# schematic3.net
KiCad netlist of a schematic drawn in EAGLE
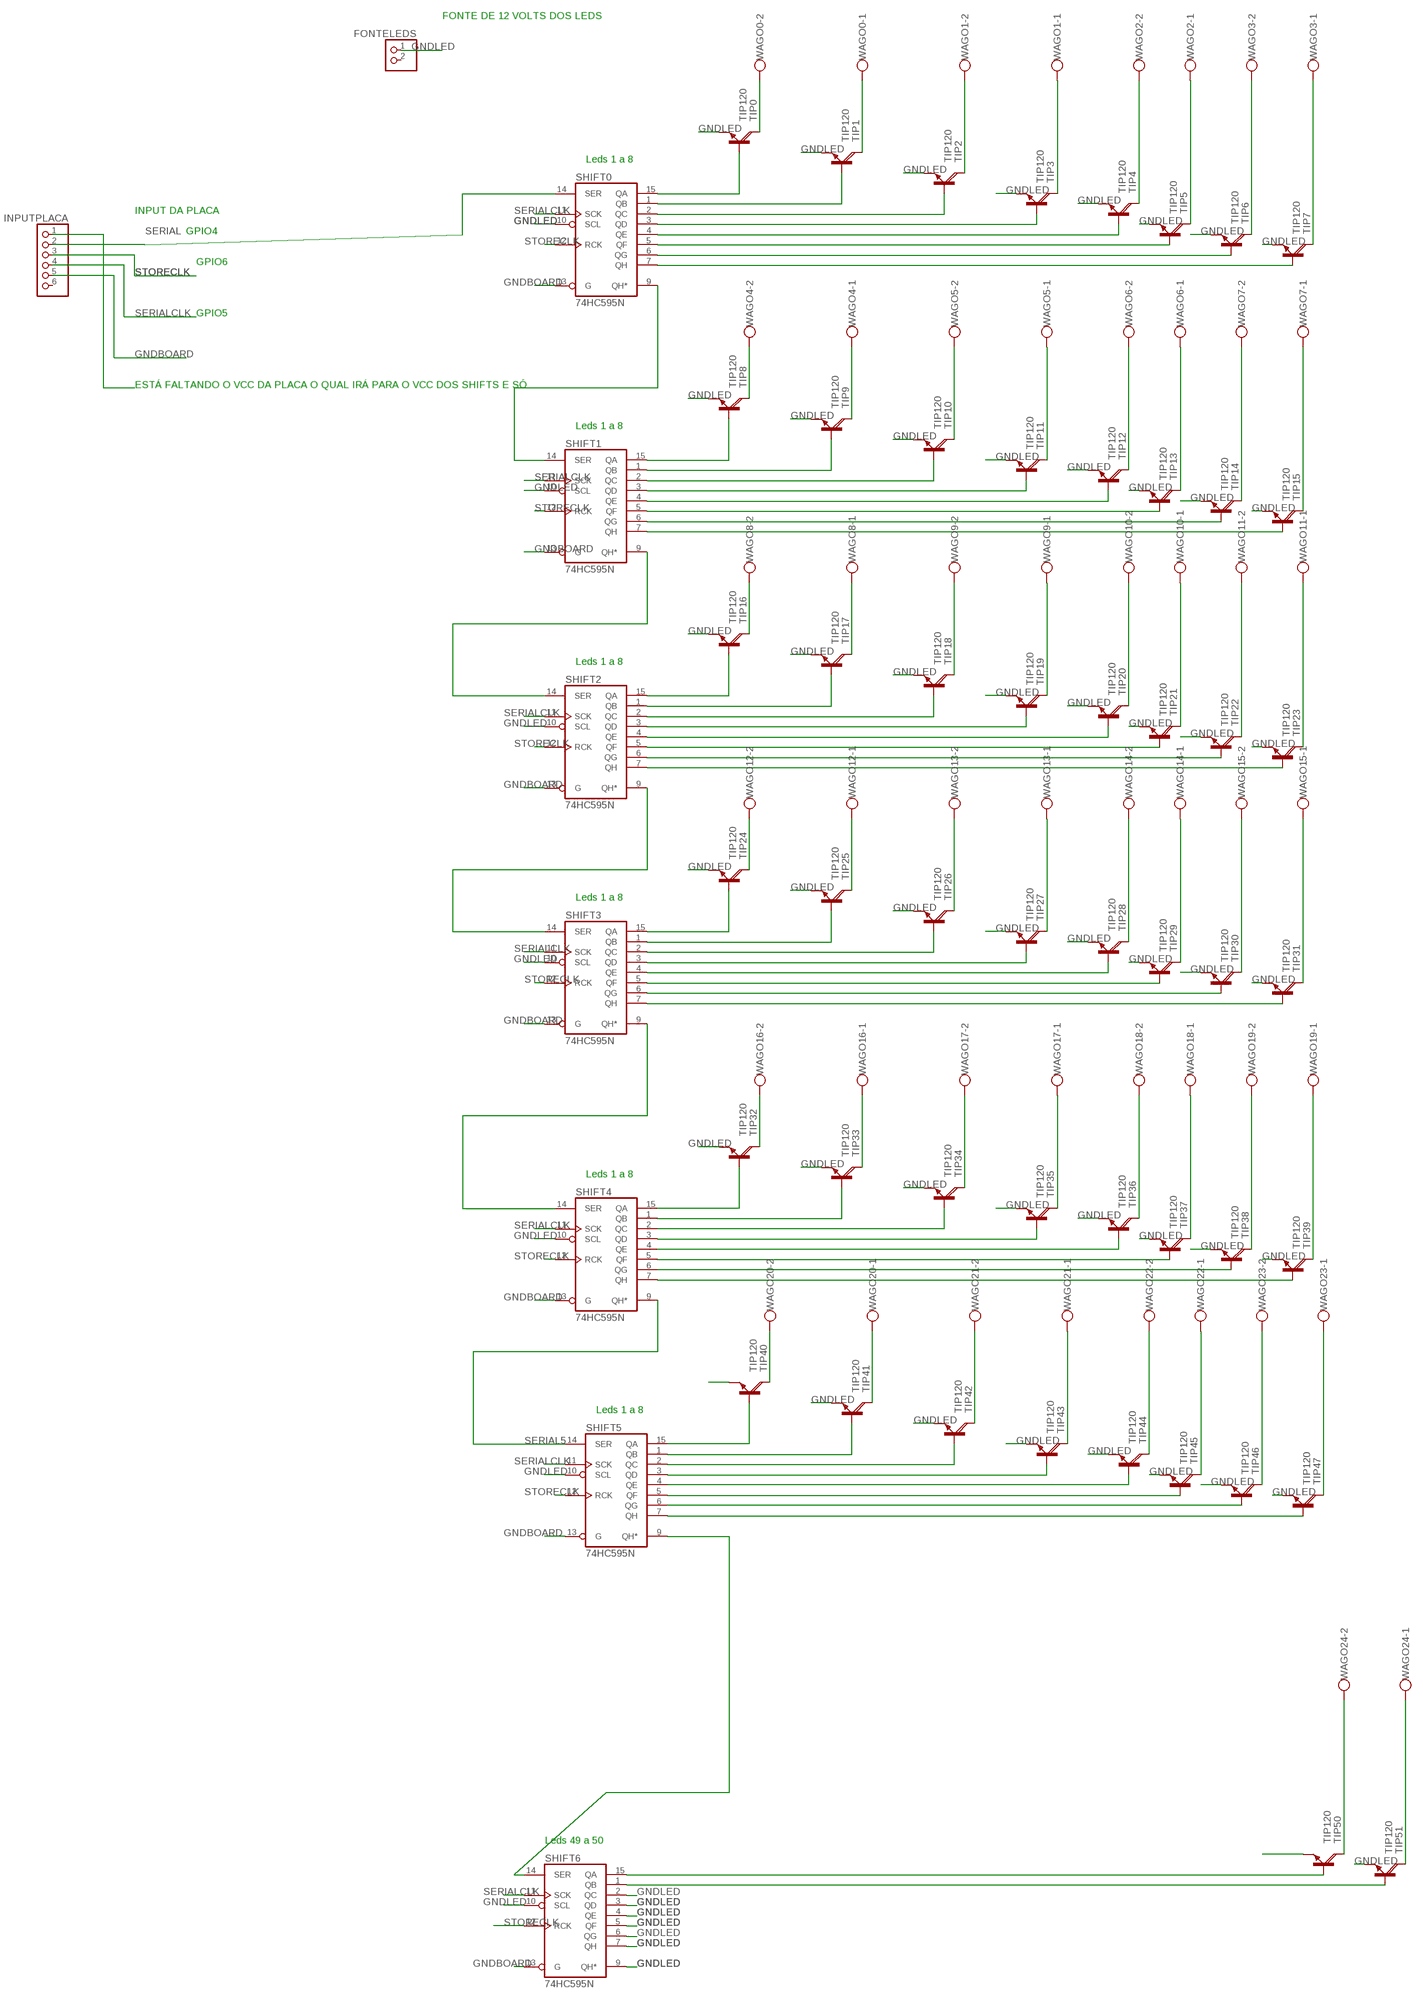
[diagram p0: schematic, sheet 1]

(export (version "E")
  (design (tool "Eeschema 10.0.6"))
  (components
    (comp (ref "FONTELEDS")
      (value "PINHD-1X2")
      (footprint "eagle-import:1X02")
      (libsource (lib "eagle-import") (part "PINHD-1X2"))
    )
    (comp (ref "INPUTPLACA")
      (value "PINHD-1X6")
      (footprint "eagle-import:1X06")
      (libsource (lib "eagle-import") (part "PINHD-1X6"))
    )
    (comp (ref "SHIFT0")
      (value "74HC595N")
      (footprint "eagle-import:DIL16")
      (libsource (lib "eagle-import") (part "74595NHC"))
    )
    (comp (ref "SHIFT1")
      (value "74HC595N")
      (footprint "eagle-import:DIL16")
      (libsource (lib "eagle-import") (part "74595NHC"))
    )
    (comp (ref "SHIFT2")
      (value "74HC595N")
      (footprint "eagle-import:DIL16")
      (libsource (lib "eagle-import") (part "74595NHC"))
    )
    (comp (ref "SHIFT3")
      (value "74HC595N")
      (footprint "eagle-import:DIL16")
      (libsource (lib "eagle-import") (part "74595NHC"))
    )
    (comp (ref "SHIFT4")
      (value "74HC595N")
      (footprint "eagle-import:DIL16")
      (libsource (lib "eagle-import") (part "74595NHC"))
    )
    (comp (ref "SHIFT5")
      (value "74HC595N")
      (footprint "eagle-import:DIL16")
      (libsource (lib "eagle-import") (part "74595NHC"))
    )
    (comp (ref "SHIFT6")
      (value "74HC595N")
      (footprint "eagle-import:DIL16")
      (libsource (lib "eagle-import") (part "74595NHC"))
    )
    (comp (ref "TIP0")
      (value "TIP120")
      (footprint "eagle-import:TO220AH")
      (libsource (lib "eagle-import") (part "TIP120"))
    )
    (comp (ref "TIP1")
      (value "TIP120")
      (footprint "eagle-import:TO220AH")
      (libsource (lib "eagle-import") (part "TIP120"))
    )
    (comp (ref "TIP2")
      (value "TIP120")
      (footprint "eagle-import:TO220AH")
      (libsource (lib "eagle-import") (part "TIP120"))
    )
    (comp (ref "TIP3")
      (value "TIP120")
      (footprint "eagle-import:TO220AH")
      (libsource (lib "eagle-import") (part "TIP120"))
    )
    (comp (ref "TIP4")
      (value "TIP120")
      (footprint "eagle-import:TO220AH")
      (libsource (lib "eagle-import") (part "TIP120"))
    )
    (comp (ref "TIP5")
      (value "TIP120")
      (footprint "eagle-import:TO220AH")
      (libsource (lib "eagle-import") (part "TIP120"))
    )
    (comp (ref "TIP6")
      (value "TIP120")
      (footprint "eagle-import:TO220AH")
      (libsource (lib "eagle-import") (part "TIP120"))
    )
    (comp (ref "TIP7")
      (value "TIP120")
      (footprint "eagle-import:TO220AH")
      (libsource (lib "eagle-import") (part "TIP120"))
    )
    (comp (ref "TIP8")
      (value "TIP120")
      (footprint "eagle-import:TO220AH")
      (libsource (lib "eagle-import") (part "TIP120"))
    )
    (comp (ref "TIP9")
      (value "TIP120")
      (footprint "eagle-import:TO220AH")
      (libsource (lib "eagle-import") (part "TIP120"))
    )
    (comp (ref "TIP10")
      (value "TIP120")
      (footprint "eagle-import:TO220AH")
      (libsource (lib "eagle-import") (part "TIP120"))
    )
    (comp (ref "TIP11")
      (value "TIP120")
      (footprint "eagle-import:TO220AH")
      (libsource (lib "eagle-import") (part "TIP120"))
    )
    (comp (ref "TIP12")
      (value "TIP120")
      (footprint "eagle-import:TO220AH")
      (libsource (lib "eagle-import") (part "TIP120"))
    )
    (comp (ref "TIP13")
      (value "TIP120")
      (footprint "eagle-import:TO220AH")
      (libsource (lib "eagle-import") (part "TIP120"))
    )
    (comp (ref "TIP14")
      (value "TIP120")
      (footprint "eagle-import:TO220AH")
      (libsource (lib "eagle-import") (part "TIP120"))
    )
    (comp (ref "TIP15")
      (value "TIP120")
      (footprint "eagle-import:TO220AH")
      (libsource (lib "eagle-import") (part "TIP120"))
    )
    (comp (ref "TIP16")
      (value "TIP120")
      (footprint "eagle-import:TO220AH")
      (libsource (lib "eagle-import") (part "TIP120"))
    )
    (comp (ref "TIP17")
      (value "TIP120")
      (footprint "eagle-import:TO220AH")
      (libsource (lib "eagle-import") (part "TIP120"))
    )
    (comp (ref "TIP18")
      (value "TIP120")
      (footprint "eagle-import:TO220AH")
      (libsource (lib "eagle-import") (part "TIP120"))
    )
    (comp (ref "TIP19")
      (value "TIP120")
      (footprint "eagle-import:TO220AH")
      (libsource (lib "eagle-import") (part "TIP120"))
    )
    (comp (ref "TIP20")
      (value "TIP120")
      (footprint "eagle-import:TO220AH")
      (libsource (lib "eagle-import") (part "TIP120"))
    )
    (comp (ref "TIP21")
      (value "TIP120")
      (footprint "eagle-import:TO220AH")
      (libsource (lib "eagle-import") (part "TIP120"))
    )
    (comp (ref "TIP22")
      (value "TIP120")
      (footprint "eagle-import:TO220AH")
      (libsource (lib "eagle-import") (part "TIP120"))
    )
    (comp (ref "TIP23")
      (value "TIP120")
      (footprint "eagle-import:TO220AH")
      (libsource (lib "eagle-import") (part "TIP120"))
    )
    (comp (ref "TIP24")
      (value "TIP120")
      (footprint "eagle-import:TO220AH")
      (libsource (lib "eagle-import") (part "TIP120"))
    )
    (comp (ref "TIP25")
      (value "TIP120")
      (footprint "eagle-import:TO220AH")
      (libsource (lib "eagle-import") (part "TIP120"))
    )
    (comp (ref "TIP26")
      (value "TIP120")
      (footprint "eagle-import:TO220AH")
      (libsource (lib "eagle-import") (part "TIP120"))
    )
    (comp (ref "TIP27")
      (value "TIP120")
      (footprint "eagle-import:TO220AH")
      (libsource (lib "eagle-import") (part "TIP120"))
    )
    (comp (ref "TIP28")
      (value "TIP120")
      (footprint "eagle-import:TO220AH")
      (libsource (lib "eagle-import") (part "TIP120"))
    )
    (comp (ref "TIP29")
      (value "TIP120")
      (footprint "eagle-import:TO220AH")
      (libsource (lib "eagle-import") (part "TIP120"))
    )
    (comp (ref "TIP30")
      (value "TIP120")
      (footprint "eagle-import:TO220AH")
      (libsource (lib "eagle-import") (part "TIP120"))
    )
    (comp (ref "TIP31")
      (value "TIP120")
      (footprint "eagle-import:TO220AH")
      (libsource (lib "eagle-import") (part "TIP120"))
    )
    (comp (ref "TIP32")
      (value "TIP120")
      (footprint "eagle-import:TO220AH")
      (libsource (lib "eagle-import") (part "TIP120"))
    )
    (comp (ref "TIP33")
      (value "TIP120")
      (footprint "eagle-import:TO220AH")
      (libsource (lib "eagle-import") (part "TIP120"))
    )
    (comp (ref "TIP34")
      (value "TIP120")
      (footprint "eagle-import:TO220AH")
      (libsource (lib "eagle-import") (part "TIP120"))
    )
    (comp (ref "TIP35")
      (value "TIP120")
      (footprint "eagle-import:TO220AH")
      (libsource (lib "eagle-import") (part "TIP120"))
    )
    (comp (ref "TIP36")
      (value "TIP120")
      (footprint "eagle-import:TO220AH")
      (libsource (lib "eagle-import") (part "TIP120"))
    )
    (comp (ref "TIP37")
      (value "TIP120")
      (footprint "eagle-import:TO220AH")
      (libsource (lib "eagle-import") (part "TIP120"))
    )
    (comp (ref "TIP38")
      (value "TIP120")
      (footprint "eagle-import:TO220AH")
      (libsource (lib "eagle-import") (part "TIP120"))
    )
    (comp (ref "TIP39")
      (value "TIP120")
      (footprint "eagle-import:TO220AH")
      (libsource (lib "eagle-import") (part "TIP120"))
    )
    (comp (ref "TIP40")
      (value "TIP120")
      (footprint "eagle-import:TO220AH")
      (libsource (lib "eagle-import") (part "TIP120"))
    )
    (comp (ref "TIP41")
      (value "TIP120")
      (footprint "eagle-import:TO220AH")
      (libsource (lib "eagle-import") (part "TIP120"))
    )
    (comp (ref "TIP42")
      (value "TIP120")
      (footprint "eagle-import:TO220AH")
      (libsource (lib "eagle-import") (part "TIP120"))
    )
    (comp (ref "TIP43")
      (value "TIP120")
      (footprint "eagle-import:TO220AH")
      (libsource (lib "eagle-import") (part "TIP120"))
    )
    (comp (ref "TIP44")
      (value "TIP120")
      (footprint "eagle-import:TO220AH")
      (libsource (lib "eagle-import") (part "TIP120"))
    )
    (comp (ref "TIP45")
      (value "TIP120")
      (footprint "eagle-import:TO220AH")
      (libsource (lib "eagle-import") (part "TIP120"))
    )
    (comp (ref "TIP46")
      (value "TIP120")
      (footprint "eagle-import:TO220AH")
      (libsource (lib "eagle-import") (part "TIP120"))
    )
    (comp (ref "TIP47")
      (value "TIP120")
      (footprint "eagle-import:TO220AH")
      (libsource (lib "eagle-import") (part "TIP120"))
    )
    (comp (ref "TIP50")
      (value "TIP120")
      (footprint "eagle-import:TO220AH")
      (libsource (lib "eagle-import") (part "TIP120"))
    )
    (comp (ref "TIP51")
      (value "TIP120")
      (footprint "eagle-import:TO220AH")
      (libsource (lib "eagle-import") (part "TIP120"))
    )
    (comp (ref "WAGO0")
      (value "W237-102")
      (footprint "eagle-import:W237-102")
      (fields (field (name "MPN") "237-102"))
      (libsource (lib "eagle-import") (part "W237-102"))
    )
    (comp (ref "WAGO1")
      (value "W237-102")
      (footprint "eagle-import:W237-102")
      (fields (field (name "MPN") "237-102"))
      (libsource (lib "eagle-import") (part "W237-102"))
    )
    (comp (ref "WAGO2")
      (value "W237-102")
      (footprint "eagle-import:W237-102")
      (fields (field (name "MPN") "237-102"))
      (libsource (lib "eagle-import") (part "W237-102"))
    )
    (comp (ref "WAGO3")
      (value "W237-102")
      (footprint "eagle-import:W237-102")
      (fields (field (name "MPN") "237-102"))
      (libsource (lib "eagle-import") (part "W237-102"))
    )
    (comp (ref "WAGO4")
      (value "W237-102")
      (footprint "eagle-import:W237-102")
      (fields (field (name "MPN") "237-102"))
      (libsource (lib "eagle-import") (part "W237-102"))
    )
    (comp (ref "WAGO5")
      (value "W237-102")
      (footprint "eagle-import:W237-102")
      (fields (field (name "MPN") "237-102"))
      (libsource (lib "eagle-import") (part "W237-102"))
    )
    (comp (ref "WAGO6")
      (value "W237-102")
      (footprint "eagle-import:W237-102")
      (fields (field (name "MPN") "237-102"))
      (libsource (lib "eagle-import") (part "W237-102"))
    )
    (comp (ref "WAGO7")
      (value "W237-102")
      (footprint "eagle-import:W237-102")
      (fields (field (name "MPN") "237-102"))
      (libsource (lib "eagle-import") (part "W237-102"))
    )
    (comp (ref "WAGO8")
      (value "W237-102")
      (footprint "eagle-import:W237-102")
      (fields (field (name "MPN") "237-102"))
      (libsource (lib "eagle-import") (part "W237-102"))
    )
    (comp (ref "WAGO9")
      (value "W237-102")
      (footprint "eagle-import:W237-102")
      (fields (field (name "MPN") "237-102"))
      (libsource (lib "eagle-import") (part "W237-102"))
    )
    (comp (ref "WAGO10")
      (value "W237-102")
      (footprint "eagle-import:W237-102")
      (fields (field (name "MPN") "237-102"))
      (libsource (lib "eagle-import") (part "W237-102"))
    )
    (comp (ref "WAGO11")
      (value "W237-102")
      (footprint "eagle-import:W237-102")
      (fields (field (name "MPN") "237-102"))
      (libsource (lib "eagle-import") (part "W237-102"))
    )
    (comp (ref "WAGO12")
      (value "W237-102")
      (footprint "eagle-import:W237-102")
      (fields (field (name "MPN") "237-102"))
      (libsource (lib "eagle-import") (part "W237-102"))
    )
    (comp (ref "WAGO13")
      (value "W237-102")
      (footprint "eagle-import:W237-102")
      (fields (field (name "MPN") "237-102"))
      (libsource (lib "eagle-import") (part "W237-102"))
    )
    (comp (ref "WAGO14")
      (value "W237-102")
      (footprint "eagle-import:W237-102")
      (fields (field (name "MPN") "237-102"))
      (libsource (lib "eagle-import") (part "W237-102"))
    )
    (comp (ref "WAGO15")
      (value "W237-102")
      (footprint "eagle-import:W237-102")
      (fields (field (name "MPN") "237-102"))
      (libsource (lib "eagle-import") (part "W237-102"))
    )
    (comp (ref "WAGO16")
      (value "W237-102")
      (footprint "eagle-import:W237-102")
      (fields (field (name "MPN") "237-102"))
      (libsource (lib "eagle-import") (part "W237-102"))
    )
    (comp (ref "WAGO17")
      (value "W237-102")
      (footprint "eagle-import:W237-102")
      (fields (field (name "MPN") "237-102"))
      (libsource (lib "eagle-import") (part "W237-102"))
    )
    (comp (ref "WAGO18")
      (value "W237-102")
      (footprint "eagle-import:W237-102")
      (fields (field (name "MPN") "237-102"))
      (libsource (lib "eagle-import") (part "W237-102"))
    )
    (comp (ref "WAGO19")
      (value "W237-102")
      (footprint "eagle-import:W237-102")
      (fields (field (name "MPN") "237-102"))
      (libsource (lib "eagle-import") (part "W237-102"))
    )
    (comp (ref "WAGO20")
      (value "W237-102")
      (footprint "eagle-import:W237-102")
      (fields (field (name "MPN") "237-102"))
      (libsource (lib "eagle-import") (part "W237-102"))
    )
    (comp (ref "WAGO21")
      (value "W237-102")
      (footprint "eagle-import:W237-102")
      (fields (field (name "MPN") "237-102"))
      (libsource (lib "eagle-import") (part "W237-102"))
    )
    (comp (ref "WAGO22")
      (value "W237-102")
      (footprint "eagle-import:W237-102")
      (fields (field (name "MPN") "237-102"))
      (libsource (lib "eagle-import") (part "W237-102"))
    )
    (comp (ref "WAGO23")
      (value "W237-102")
      (footprint "eagle-import:W237-102")
      (fields (field (name "MPN") "237-102"))
      (libsource (lib "eagle-import") (part "W237-102"))
    )
    (comp (ref "WAGO24")
      (value "W237-102")
      (footprint "eagle-import:W237-102")
      (fields (field (name "MPN") "237-102"))
      (libsource (lib "eagle-import") (part "W237-102"))
    )
  )
  (nets
    (net (code "1") (name "/GNDBOARD") (class "Default")
      (node (ref "INPUTPLACA") (pin "5") (pinfunction "5_5") (pintype "passive"))
      (node (ref "SHIFT0") (pin "13") (pinfunction "G_13") (pintype "input"))
      (node (ref "SHIFT1") (pin "13") (pinfunction "G_13") (pintype "input"))
      (node (ref "SHIFT2") (pin "13") (pinfunction "G_13") (pintype "input"))
      (node (ref "SHIFT3") (pin "13") (pinfunction "G_13") (pintype "input"))
      (node (ref "SHIFT4") (pin "13") (pinfunction "G_13") (pintype "input"))
      (node (ref "SHIFT5") (pin "13") (pinfunction "G_13") (pintype "input"))
      (node (ref "SHIFT6") (pin "13") (pinfunction "G_13") (pintype "input"))
    )
    (net (code "2") (name "/GNDLED") (class "Default")
      (node (ref "FONTELEDS") (pin "1") (pinfunction "1_1") (pintype "passive"))
      (node (ref "SHIFT0") (pin "10") (pinfunction "SCL_10") (pintype "input"))
      (node (ref "SHIFT1") (pin "10") (pinfunction "SCL_10") (pintype "input"))
      (node (ref "SHIFT2") (pin "10") (pinfunction "SCL_10") (pintype "input"))
      (node (ref "SHIFT3") (pin "10") (pinfunction "SCL_10") (pintype "input"))
      (node (ref "SHIFT4") (pin "10") (pinfunction "SCL_10") (pintype "input"))
      (node (ref "SHIFT5") (pin "10") (pinfunction "SCL_10") (pintype "input"))
      (node (ref "SHIFT6") (pin "10") (pinfunction "SCL_10") (pintype "input"))
      (node (ref "SHIFT6") (pin "2") (pinfunction "QC_2") (pintype "tri_state"))
      (node (ref "SHIFT6") (pin "3") (pinfunction "QD_3") (pintype "tri_state"))
      (node (ref "SHIFT6") (pin "4") (pinfunction "QE_4") (pintype "tri_state"))
      (node (ref "SHIFT6") (pin "5") (pinfunction "QF_5") (pintype "tri_state"))
      (node (ref "SHIFT6") (pin "6") (pinfunction "QG_6") (pintype "tri_state"))
      (node (ref "SHIFT6") (pin "7") (pinfunction "QH_7") (pintype "tri_state"))
      (node (ref "SHIFT6") (pin "9") (pinfunction "QH*_9") (pintype "tri_state"))
      (node (ref "TIP0") (pin "E") (pinfunction "E_E") (pintype "passive"))
      (node (ref "TIP1") (pin "E") (pinfunction "E_E") (pintype "passive"))
      (node (ref "TIP10") (pin "E") (pinfunction "E_E") (pintype "passive"))
      (node (ref "TIP11") (pin "E") (pinfunction "E_E") (pintype "passive"))
      (node (ref "TIP12") (pin "E") (pinfunction "E_E") (pintype "passive"))
      (node (ref "TIP13") (pin "E") (pinfunction "E_E") (pintype "passive"))
      (node (ref "TIP14") (pin "E") (pinfunction "E_E") (pintype "passive"))
      (node (ref "TIP15") (pin "E") (pinfunction "E_E") (pintype "passive"))
      (node (ref "TIP16") (pin "E") (pinfunction "E_E") (pintype "passive"))
      (node (ref "TIP17") (pin "E") (pinfunction "E_E") (pintype "passive"))
      (node (ref "TIP18") (pin "E") (pinfunction "E_E") (pintype "passive"))
      (node (ref "TIP19") (pin "E") (pinfunction "E_E") (pintype "passive"))
      (node (ref "TIP2") (pin "E") (pinfunction "E_E") (pintype "passive"))
      (node (ref "TIP20") (pin "E") (pinfunction "E_E") (pintype "passive"))
      (node (ref "TIP21") (pin "E") (pinfunction "E_E") (pintype "passive"))
      (node (ref "TIP22") (pin "E") (pinfunction "E_E") (pintype "passive"))
      (node (ref "TIP23") (pin "E") (pinfunction "E_E") (pintype "passive"))
      (node (ref "TIP24") (pin "E") (pinfunction "E_E") (pintype "passive"))
      (node (ref "TIP25") (pin "E") (pinfunction "E_E") (pintype "passive"))
      (node (ref "TIP26") (pin "E") (pinfunction "E_E") (pintype "passive"))
      (node (ref "TIP27") (pin "E") (pinfunction "E_E") (pintype "passive"))
      (node (ref "TIP28") (pin "E") (pinfunction "E_E") (pintype "passive"))
      (node (ref "TIP29") (pin "E") (pinfunction "E_E") (pintype "passive"))
      (node (ref "TIP3") (pin "E") (pinfunction "E_E") (pintype "passive"))
      (node (ref "TIP30") (pin "E") (pinfunction "E_E") (pintype "passive"))
      (node (ref "TIP31") (pin "E") (pinfunction "E_E") (pintype "passive"))
      (node (ref "TIP32") (pin "E") (pinfunction "E_E") (pintype "passive"))
      (node (ref "TIP33") (pin "E") (pinfunction "E_E") (pintype "passive"))
      (node (ref "TIP34") (pin "E") (pinfunction "E_E") (pintype "passive"))
      (node (ref "TIP35") (pin "E") (pinfunction "E_E") (pintype "passive"))
      (node (ref "TIP36") (pin "E") (pinfunction "E_E") (pintype "passive"))
      (node (ref "TIP37") (pin "E") (pinfunction "E_E") (pintype "passive"))
      (node (ref "TIP38") (pin "E") (pinfunction "E_E") (pintype "passive"))
      (node (ref "TIP39") (pin "E") (pinfunction "E_E") (pintype "passive"))
      (node (ref "TIP4") (pin "E") (pinfunction "E_E") (pintype "passive"))
      (node (ref "TIP40") (pin "E") (pinfunction "E_E") (pintype "passive"))
      (node (ref "TIP41") (pin "E") (pinfunction "E_E") (pintype "passive"))
      (node (ref "TIP42") (pin "E") (pinfunction "E_E") (pintype "passive"))
      (node (ref "TIP43") (pin "E") (pinfunction "E_E") (pintype "passive"))
      (node (ref "TIP44") (pin "E") (pinfunction "E_E") (pintype "passive"))
      (node (ref "TIP45") (pin "E") (pinfunction "E_E") (pintype "passive"))
      (node (ref "TIP46") (pin "E") (pinfunction "E_E") (pintype "passive"))
      (node (ref "TIP47") (pin "E") (pinfunction "E_E") (pintype "passive"))
      (node (ref "TIP5") (pin "E") (pinfunction "E_E") (pintype "passive"))
      (node (ref "TIP50") (pin "E") (pinfunction "E_E") (pintype "passive"))
      (node (ref "TIP51") (pin "E") (pinfunction "E_E") (pintype "passive"))
      (node (ref "TIP6") (pin "E") (pinfunction "E_E") (pintype "passive"))
      (node (ref "TIP7") (pin "E") (pinfunction "E_E") (pintype "passive"))
      (node (ref "TIP8") (pin "E") (pinfunction "E_E") (pintype "passive"))
      (node (ref "TIP9") (pin "E") (pinfunction "E_E") (pintype "passive"))
    )
    (net (code "3") (name "/SERIAL") (class "Default")
      (node (ref "INPUTPLACA") (pin "2") (pinfunction "2_2") (pintype "passive"))
      (node (ref "SHIFT0") (pin "14") (pinfunction "SER_14") (pintype "input"))
    )
    (net (code "4") (name "/SERIAL5") (class "Default")
      (node (ref "SHIFT4") (pin "9") (pinfunction "QH*_9") (pintype "tri_state"))
      (node (ref "SHIFT5") (pin "14") (pinfunction "SER_14") (pintype "input"))
    )
    (net (code "5") (name "/SERIALCLK") (class "Default")
      (node (ref "INPUTPLACA") (pin "4") (pinfunction "4_4") (pintype "passive"))
      (node (ref "SHIFT0") (pin "11") (pinfunction "SCK_11") (pintype "input"))
      (node (ref "SHIFT1") (pin "11") (pinfunction "SCK_11") (pintype "input"))
      (node (ref "SHIFT2") (pin "11") (pinfunction "SCK_11") (pintype "input"))
      (node (ref "SHIFT3") (pin "11") (pinfunction "SCK_11") (pintype "input"))
      (node (ref "SHIFT4") (pin "11") (pinfunction "SCK_11") (pintype "input"))
      (node (ref "SHIFT5") (pin "11") (pinfunction "SCK_11") (pintype "input"))
      (node (ref "SHIFT6") (pin "11") (pinfunction "SCK_11") (pintype "input"))
    )
    (net (code "6") (name "/STORECLK") (class "Default")
      (node (ref "INPUTPLACA") (pin "3") (pinfunction "3_3") (pintype "passive"))
      (node (ref "SHIFT0") (pin "12") (pinfunction "RCK_12") (pintype "input"))
      (node (ref "SHIFT1") (pin "12") (pinfunction "RCK_12") (pintype "input"))
      (node (ref "SHIFT2") (pin "12") (pinfunction "RCK_12") (pintype "input"))
      (node (ref "SHIFT3") (pin "12") (pinfunction "RCK_12") (pintype "input"))
      (node (ref "SHIFT4") (pin "12") (pinfunction "RCK_12") (pintype "input"))
      (node (ref "SHIFT5") (pin "12") (pinfunction "RCK_12") (pintype "input"))
      (node (ref "SHIFT6") (pin "12") (pinfunction "RCK_12") (pintype "input"))
    )
    (net (code "7") (name "Net-(SHIFT0A-QA)") (class "Default")
      (node (ref "SHIFT0") (pin "15") (pinfunction "QA_15") (pintype "tri_state"))
      (node (ref "TIP0") (pin "B") (pinfunction "B_B") (pintype "passive"))
    )
    (net (code "8") (name "Net-(SHIFT0A-QB)") (class "Default")
      (node (ref "SHIFT0") (pin "1") (pinfunction "QB_1") (pintype "tri_state"))
      (node (ref "TIP1") (pin "B") (pinfunction "B_B") (pintype "passive"))
    )
    (net (code "9") (name "Net-(SHIFT0A-QC)") (class "Default")
      (node (ref "SHIFT0") (pin "2") (pinfunction "QC_2") (pintype "tri_state"))
      (node (ref "TIP2") (pin "B") (pinfunction "B_B") (pintype "passive"))
    )
    (net (code "10") (name "Net-(SHIFT0A-QD)") (class "Default")
      (node (ref "SHIFT0") (pin "3") (pinfunction "QD_3") (pintype "tri_state"))
      (node (ref "TIP3") (pin "B") (pinfunction "B_B") (pintype "passive"))
    )
    (net (code "11") (name "Net-(SHIFT0A-QE)") (class "Default")
      (node (ref "SHIFT0") (pin "4") (pinfunction "QE_4") (pintype "tri_state"))
      (node (ref "TIP4") (pin "B") (pinfunction "B_B") (pintype "passive"))
    )
    (net (code "12") (name "Net-(SHIFT0A-QF)") (class "Default")
      (node (ref "SHIFT0") (pin "5") (pinfunction "QF_5") (pintype "tri_state"))
      (node (ref "TIP5") (pin "B") (pinfunction "B_B") (pintype "passive"))
    )
    (net (code "13") (name "Net-(SHIFT0A-QG)") (class "Default")
      (node (ref "SHIFT0") (pin "6") (pinfunction "QG_6") (pintype "tri_state"))
      (node (ref "TIP6") (pin "B") (pinfunction "B_B") (pintype "passive"))
    )
    (net (code "14") (name "Net-(SHIFT0A-QH)") (class "Default")
      (node (ref "SHIFT0") (pin "7") (pinfunction "QH_7") (pintype "tri_state"))
      (node (ref "TIP7") (pin "B") (pinfunction "B_B") (pintype "passive"))
    )
    (net (code "15") (name "Net-(SHIFT0A-QH*)") (class "Default")
      (node (ref "SHIFT0") (pin "9") (pinfunction "QH*_9") (pintype "tri_state"))
      (node (ref "SHIFT1") (pin "14") (pinfunction "SER_14") (pintype "input"))
    )
    (net (code "16") (name "Net-(SHIFT1A-QA)") (class "Default")
      (node (ref "SHIFT1") (pin "15") (pinfunction "QA_15") (pintype "tri_state"))
      (node (ref "TIP8") (pin "B") (pinfunction "B_B") (pintype "passive"))
    )
    (net (code "17") (name "Net-(SHIFT1A-QB)") (class "Default")
      (node (ref "SHIFT1") (pin "1") (pinfunction "QB_1") (pintype "tri_state"))
      (node (ref "TIP9") (pin "B") (pinfunction "B_B") (pintype "passive"))
    )
    (net (code "18") (name "Net-(SHIFT1A-QC)") (class "Default")
      (node (ref "SHIFT1") (pin "2") (pinfunction "QC_2") (pintype "tri_state"))
      (node (ref "TIP10") (pin "B") (pinfunction "B_B") (pintype "passive"))
    )
    (net (code "19") (name "Net-(SHIFT1A-QD)") (class "Default")
      (node (ref "SHIFT1") (pin "3") (pinfunction "QD_3") (pintype "tri_state"))
      (node (ref "TIP11") (pin "B") (pinfunction "B_B") (pintype "passive"))
    )
    (net (code "20") (name "Net-(SHIFT1A-QE)") (class "Default")
      (node (ref "SHIFT1") (pin "4") (pinfunction "QE_4") (pintype "tri_state"))
      (node (ref "TIP12") (pin "B") (pinfunction "B_B") (pintype "passive"))
    )
    (net (code "21") (name "Net-(SHIFT1A-QF)") (class "Default")
      (node (ref "SHIFT1") (pin "5") (pinfunction "QF_5") (pintype "tri_state"))
      (node (ref "TIP13") (pin "B") (pinfunction "B_B") (pintype "passive"))
    )
    (net (code "22") (name "Net-(SHIFT1A-QG)") (class "Default")
      (node (ref "SHIFT1") (pin "6") (pinfunction "QG_6") (pintype "tri_state"))
      (node (ref "TIP14") (pin "B") (pinfunction "B_B") (pintype "passive"))
    )
    (net (code "23") (name "Net-(SHIFT1A-QH)") (class "Default")
      (node (ref "SHIFT1") (pin "7") (pinfunction "QH_7") (pintype "tri_state"))
      (node (ref "TIP15") (pin "B") (pinfunction "B_B") (pintype "passive"))
    )
    (net (code "24") (name "Net-(SHIFT1A-QH*)") (class "Default")
      (node (ref "SHIFT1") (pin "9") (pinfunction "QH*_9") (pintype "tri_state"))
      (node (ref "SHIFT2") (pin "14") (pinfunction "SER_14") (pintype "input"))
    )
    (net (code "25") (name "Net-(SHIFT2A-QA)") (class "Default")
      (node (ref "SHIFT2") (pin "15") (pinfunction "QA_15") (pintype "tri_state"))
      (node (ref "TIP16") (pin "B") (pinfunction "B_B") (pintype "passive"))
    )
    (net (code "26") (name "Net-(SHIFT2A-QB)") (class "Default")
      (node (ref "SHIFT2") (pin "1") (pinfunction "QB_1") (pintype "tri_state"))
      (node (ref "TIP17") (pin "B") (pinfunction "B_B") (pintype "passive"))
    )
    (net (code "27") (name "Net-(SHIFT2A-QC)") (class "Default")
      (node (ref "SHIFT2") (pin "2") (pinfunction "QC_2") (pintype "tri_state"))
      (node (ref "TIP18") (pin "B") (pinfunction "B_B") (pintype "passive"))
    )
    (net (code "28") (name "Net-(SHIFT2A-QD)") (class "Default")
      (node (ref "SHIFT2") (pin "3") (pinfunction "QD_3") (pintype "tri_state"))
      (node (ref "TIP19") (pin "B") (pinfunction "B_B") (pintype "passive"))
    )
    (net (code "29") (name "Net-(SHIFT2A-QE)") (class "Default")
      (node (ref "SHIFT2") (pin "4") (pinfunction "QE_4") (pintype "tri_state"))
      (node (ref "TIP20") (pin "B") (pinfunction "B_B") (pintype "passive"))
    )
    (net (code "30") (name "Net-(SHIFT2A-QF)") (class "Default")
      (node (ref "SHIFT2") (pin "5") (pinfunction "QF_5") (pintype "tri_state"))
      (node (ref "TIP21") (pin "B") (pinfunction "B_B") (pintype "passive"))
    )
    (net (code "31") (name "Net-(SHIFT2A-QG)") (class "Default")
      (node (ref "SHIFT2") (pin "6") (pinfunction "QG_6") (pintype "tri_state"))
      (node (ref "TIP22") (pin "B") (pinfunction "B_B") (pintype "passive"))
    )
    (net (code "32") (name "Net-(SHIFT2A-QH)") (class "Default")
      (node (ref "SHIFT2") (pin "7") (pinfunction "QH_7") (pintype "tri_state"))
      (node (ref "TIP23") (pin "B") (pinfunction "B_B") (pintype "passive"))
    )
    (net (code "33") (name "Net-(SHIFT2A-QH*)") (class "Default")
      (node (ref "SHIFT2") (pin "9") (pinfunction "QH*_9") (pintype "tri_state"))
      (node (ref "SHIFT3") (pin "14") (pinfunction "SER_14") (pintype "input"))
    )
    (net (code "34") (name "Net-(SHIFT3A-QA)") (class "Default")
      (node (ref "SHIFT3") (pin "15") (pinfunction "QA_15") (pintype "tri_state"))
      (node (ref "TIP24") (pin "B") (pinfunction "B_B") (pintype "passive"))
    )
    (net (code "35") (name "Net-(SHIFT3A-QB)") (class "Default")
      (node (ref "SHIFT3") (pin "1") (pinfunction "QB_1") (pintype "tri_state"))
      (node (ref "TIP25") (pin "B") (pinfunction "B_B") (pintype "passive"))
    )
    (net (code "36") (name "Net-(SHIFT3A-QC)") (class "Default")
      (node (ref "SHIFT3") (pin "2") (pinfunction "QC_2") (pintype "tri_state"))
      (node (ref "TIP26") (pin "B") (pinfunction "B_B") (pintype "passive"))
    )
    (net (code "37") (name "Net-(SHIFT3A-QD)") (class "Default")
      (node (ref "SHIFT3") (pin "3") (pinfunction "QD_3") (pintype "tri_state"))
      (node (ref "TIP27") (pin "B") (pinfunction "B_B") (pintype "passive"))
    )
    (net (code "38") (name "Net-(SHIFT3A-QE)") (class "Default")
      (node (ref "SHIFT3") (pin "4") (pinfunction "QE_4") (pintype "tri_state"))
      (node (ref "TIP28") (pin "B") (pinfunction "B_B") (pintype "passive"))
    )
    (net (code "39") (name "Net-(SHIFT3A-QF)") (class "Default")
      (node (ref "SHIFT3") (pin "5") (pinfunction "QF_5") (pintype "tri_state"))
      (node (ref "TIP29") (pin "B") (pinfunction "B_B") (pintype "passive"))
    )
    (net (code "40") (name "Net-(SHIFT3A-QG)") (class "Default")
      (node (ref "SHIFT3") (pin "6") (pinfunction "QG_6") (pintype "tri_state"))
      (node (ref "TIP30") (pin "B") (pinfunction "B_B") (pintype "passive"))
    )
    (net (code "41") (name "Net-(SHIFT3A-QH)") (class "Default")
      (node (ref "SHIFT3") (pin "7") (pinfunction "QH_7") (pintype "tri_state"))
      (node (ref "TIP31") (pin "B") (pinfunction "B_B") (pintype "passive"))
    )
    (net (code "42") (name "Net-(SHIFT3A-QH*)") (class "Default")
      (node (ref "SHIFT3") (pin "9") (pinfunction "QH*_9") (pintype "tri_state"))
      (node (ref "SHIFT4") (pin "14") (pinfunction "SER_14") (pintype "input"))
    )
    (net (code "43") (name "Net-(SHIFT4A-QA)") (class "Default")
      (node (ref "SHIFT4") (pin "15") (pinfunction "QA_15") (pintype "tri_state"))
      (node (ref "TIP32") (pin "B") (pinfunction "B_B") (pintype "passive"))
    )
    (net (code "44") (name "Net-(SHIFT4A-QB)") (class "Default")
      (node (ref "SHIFT4") (pin "1") (pinfunction "QB_1") (pintype "tri_state"))
      (node (ref "TIP33") (pin "B") (pinfunction "B_B") (pintype "passive"))
    )
    (net (code "45") (name "Net-(SHIFT4A-QC)") (class "Default")
      (node (ref "SHIFT4") (pin "2") (pinfunction "QC_2") (pintype "tri_state"))
      (node (ref "TIP34") (pin "B") (pinfunction "B_B") (pintype "passive"))
    )
    (net (code "46") (name "Net-(SHIFT4A-QD)") (class "Default")
      (node (ref "SHIFT4") (pin "3") (pinfunction "QD_3") (pintype "tri_state"))
      (node (ref "TIP35") (pin "B") (pinfunction "B_B") (pintype "passive"))
    )
    (net (code "47") (name "Net-(SHIFT4A-QE)") (class "Default")
      (node (ref "SHIFT4") (pin "4") (pinfunction "QE_4") (pintype "tri_state"))
      (node (ref "TIP36") (pin "B") (pinfunction "B_B") (pintype "passive"))
    )
    (net (code "48") (name "Net-(SHIFT4A-QF)") (class "Default")
      (node (ref "SHIFT4") (pin "5") (pinfunction "QF_5") (pintype "tri_state"))
      (node (ref "TIP37") (pin "B") (pinfunction "B_B") (pintype "passive"))
    )
    (net (code "49") (name "Net-(SHIFT4A-QG)") (class "Default")
      (node (ref "SHIFT4") (pin "6") (pinfunction "QG_6") (pintype "tri_state"))
      (node (ref "TIP38") (pin "B") (pinfunction "B_B") (pintype "passive"))
    )
    (net (code "50") (name "Net-(SHIFT4A-QH)") (class "Default")
      (node (ref "SHIFT4") (pin "7") (pinfunction "QH_7") (pintype "tri_state"))
      (node (ref "TIP39") (pin "B") (pinfunction "B_B") (pintype "passive"))
    )
    (net (code "51") (name "Net-(SHIFT5A-QA)") (class "Default")
      (node (ref "SHIFT5") (pin "15") (pinfunction "QA_15") (pintype "tri_state"))
      (node (ref "TIP40") (pin "B") (pinfunction "B_B") (pintype "passive"))
    )
    (net (code "52") (name "Net-(SHIFT5A-QB)") (class "Default")
      (node (ref "SHIFT5") (pin "1") (pinfunction "QB_1") (pintype "tri_state"))
      (node (ref "TIP41") (pin "B") (pinfunction "B_B") (pintype "passive"))
    )
    (net (code "53") (name "Net-(SHIFT5A-QC)") (class "Default")
      (node (ref "SHIFT5") (pin "2") (pinfunction "QC_2") (pintype "tri_state"))
      (node (ref "TIP42") (pin "B") (pinfunction "B_B") (pintype "passive"))
    )
    (net (code "54") (name "Net-(SHIFT5A-QD)") (class "Default")
      (node (ref "SHIFT5") (pin "3") (pinfunction "QD_3") (pintype "tri_state"))
      (node (ref "TIP43") (pin "B") (pinfunction "B_B") (pintype "passive"))
    )
    (net (code "55") (name "Net-(SHIFT5A-QE)") (class "Default")
      (node (ref "SHIFT5") (pin "4") (pinfunction "QE_4") (pintype "tri_state"))
      (node (ref "TIP44") (pin "B") (pinfunction "B_B") (pintype "passive"))
    )
    (net (code "56") (name "Net-(SHIFT5A-QF)") (class "Default")
      (node (ref "SHIFT5") (pin "5") (pinfunction "QF_5") (pintype "tri_state"))
      (node (ref "TIP45") (pin "B") (pinfunction "B_B") (pintype "passive"))
    )
    (net (code "57") (name "Net-(SHIFT5A-QG)") (class "Default")
      (node (ref "SHIFT5") (pin "6") (pinfunction "QG_6") (pintype "tri_state"))
      (node (ref "TIP46") (pin "B") (pinfunction "B_B") (pintype "passive"))
    )
    (net (code "58") (name "Net-(SHIFT5A-QH)") (class "Default")
      (node (ref "SHIFT5") (pin "7") (pinfunction "QH_7") (pintype "tri_state"))
      (node (ref "TIP47") (pin "B") (pinfunction "B_B") (pintype "passive"))
    )
    (net (code "59") (name "Net-(SHIFT5A-QH*)") (class "Default")
      (node (ref "SHIFT5") (pin "9") (pinfunction "QH*_9") (pintype "tri_state"))
      (node (ref "SHIFT6") (pin "14") (pinfunction "SER_14") (pintype "input"))
    )
    (net (code "60") (name "Net-(SHIFT6A-QA)") (class "Default")
      (node (ref "SHIFT6") (pin "15") (pinfunction "QA_15") (pintype "tri_state"))
      (node (ref "TIP50") (pin "B") (pinfunction "B_B") (pintype "passive"))
    )
    (net (code "61") (name "Net-(SHIFT6A-QB)") (class "Default")
      (node (ref "SHIFT6") (pin "1") (pinfunction "QB_1") (pintype "tri_state"))
      (node (ref "TIP51") (pin "B") (pinfunction "B_B") (pintype "passive"))
    )
    (net (code "62") (name "Net-(WAGO0A-KL)") (class "Default")
      (node (ref "TIP1") (pin "C") (pinfunction "C_C") (pintype "passive"))
      (node (ref "WAGO0") (pin "1") (pinfunction "KL_1") (pintype "passive"))
    )
    (net (code "63") (name "Net-(WAGO0B-KL)") (class "Default")
      (node (ref "TIP0") (pin "C") (pinfunction "C_C") (pintype "passive"))
      (node (ref "WAGO0") (pin "2") (pinfunction "KL_2") (pintype "passive"))
    )
    (net (code "64") (name "Net-(WAGO1A-KL)") (class "Default")
      (node (ref "TIP3") (pin "C") (pinfunction "C_C") (pintype "passive"))
      (node (ref "WAGO1") (pin "1") (pinfunction "KL_1") (pintype "passive"))
    )
    (net (code "65") (name "Net-(WAGO1B-KL)") (class "Default")
      (node (ref "TIP2") (pin "C") (pinfunction "C_C") (pintype "passive"))
      (node (ref "WAGO1") (pin "2") (pinfunction "KL_2") (pintype "passive"))
    )
    (net (code "66") (name "Net-(WAGO2A-KL)") (class "Default")
      (node (ref "TIP5") (pin "C") (pinfunction "C_C") (pintype "passive"))
      (node (ref "WAGO2") (pin "1") (pinfunction "KL_1") (pintype "passive"))
    )
    (net (code "67") (name "Net-(WAGO2B-KL)") (class "Default")
      (node (ref "TIP4") (pin "C") (pinfunction "C_C") (pintype "passive"))
      (node (ref "WAGO2") (pin "2") (pinfunction "KL_2") (pintype "passive"))
    )
    (net (code "68") (name "Net-(WAGO3A-KL)") (class "Default")
      (node (ref "TIP7") (pin "C") (pinfunction "C_C") (pintype "passive"))
      (node (ref "WAGO3") (pin "1") (pinfunction "KL_1") (pintype "passive"))
    )
    (net (code "69") (name "Net-(WAGO3B-KL)") (class "Default")
      (node (ref "TIP6") (pin "C") (pinfunction "C_C") (pintype "passive"))
      (node (ref "WAGO3") (pin "2") (pinfunction "KL_2") (pintype "passive"))
    )
    (net (code "70") (name "Net-(WAGO4A-KL)") (class "Default")
      (node (ref "TIP9") (pin "C") (pinfunction "C_C") (pintype "passive"))
      (node (ref "WAGO4") (pin "1") (pinfunction "KL_1") (pintype "passive"))
    )
    (net (code "71") (name "Net-(WAGO4B-KL)") (class "Default")
      (node (ref "TIP8") (pin "C") (pinfunction "C_C") (pintype "passive"))
      (node (ref "WAGO4") (pin "2") (pinfunction "KL_2") (pintype "passive"))
    )
    (net (code "72") (name "Net-(WAGO5A-KL)") (class "Default")
      (node (ref "TIP11") (pin "C") (pinfunction "C_C") (pintype "passive"))
      (node (ref "WAGO5") (pin "1") (pinfunction "KL_1") (pintype "passive"))
    )
    (net (code "73") (name "Net-(WAGO5B-KL)") (class "Default")
      (node (ref "TIP10") (pin "C") (pinfunction "C_C") (pintype "passive"))
      (node (ref "WAGO5") (pin "2") (pinfunction "KL_2") (pintype "passive"))
    )
    (net (code "74") (name "Net-(WAGO6A-KL)") (class "Default")
      (node (ref "TIP13") (pin "C") (pinfunction "C_C") (pintype "passive"))
      (node (ref "WAGO6") (pin "1") (pinfunction "KL_1") (pintype "passive"))
    )
    (net (code "75") (name "Net-(WAGO6B-KL)") (class "Default")
      (node (ref "TIP12") (pin "C") (pinfunction "C_C") (pintype "passive"))
      (node (ref "WAGO6") (pin "2") (pinfunction "KL_2") (pintype "passive"))
    )
    (net (code "76") (name "Net-(WAGO7A-KL)") (class "Default")
      (node (ref "TIP15") (pin "C") (pinfunction "C_C") (pintype "passive"))
      (node (ref "WAGO7") (pin "1") (pinfunction "KL_1") (pintype "passive"))
    )
    (net (code "77") (name "Net-(WAGO7B-KL)") (class "Default")
      (node (ref "TIP14") (pin "C") (pinfunction "C_C") (pintype "passive"))
      (node (ref "WAGO7") (pin "2") (pinfunction "KL_2") (pintype "passive"))
    )
    (net (code "78") (name "Net-(WAGO8A-KL)") (class "Default")
      (node (ref "TIP17") (pin "C") (pinfunction "C_C") (pintype "passive"))
      (node (ref "WAGO8") (pin "1") (pinfunction "KL_1") (pintype "passive"))
    )
    (net (code "79") (name "Net-(WAGO8B-KL)") (class "Default")
      (node (ref "TIP16") (pin "C") (pinfunction "C_C") (pintype "passive"))
      (node (ref "WAGO8") (pin "2") (pinfunction "KL_2") (pintype "passive"))
    )
    (net (code "80") (name "Net-(WAGO9A-KL)") (class "Default")
      (node (ref "TIP19") (pin "C") (pinfunction "C_C") (pintype "passive"))
      (node (ref "WAGO9") (pin "1") (pinfunction "KL_1") (pintype "passive"))
    )
    (net (code "81") (name "Net-(WAGO9B-KL)") (class "Default")
      (node (ref "TIP18") (pin "C") (pinfunction "C_C") (pintype "passive"))
      (node (ref "WAGO9") (pin "2") (pinfunction "KL_2") (pintype "passive"))
    )
    (net (code "82") (name "Net-(WAGO10A-KL)") (class "Default")
      (node (ref "TIP21") (pin "C") (pinfunction "C_C") (pintype "passive"))
      (node (ref "WAGO10") (pin "1") (pinfunction "KL_1") (pintype "passive"))
    )
    (net (code "83") (name "Net-(WAGO10B-KL)") (class "Default")
      (node (ref "TIP20") (pin "C") (pinfunction "C_C") (pintype "passive"))
      (node (ref "WAGO10") (pin "2") (pinfunction "KL_2") (pintype "passive"))
    )
    (net (code "84") (name "Net-(WAGO11A-KL)") (class "Default")
      (node (ref "TIP23") (pin "C") (pinfunction "C_C") (pintype "passive"))
      (node (ref "WAGO11") (pin "1") (pinfunction "KL_1") (pintype "passive"))
    )
    (net (code "85") (name "Net-(WAGO11B-KL)") (class "Default")
      (node (ref "TIP22") (pin "C") (pinfunction "C_C") (pintype "passive"))
      (node (ref "WAGO11") (pin "2") (pinfunction "KL_2") (pintype "passive"))
    )
    (net (code "86") (name "Net-(WAGO12A-KL)") (class "Default")
      (node (ref "TIP25") (pin "C") (pinfunction "C_C") (pintype "passive"))
      (node (ref "WAGO12") (pin "1") (pinfunction "KL_1") (pintype "passive"))
    )
    (net (code "87") (name "Net-(WAGO12B-KL)") (class "Default")
      (node (ref "TIP24") (pin "C") (pinfunction "C_C") (pintype "passive"))
      (node (ref "WAGO12") (pin "2") (pinfunction "KL_2") (pintype "passive"))
    )
    (net (code "88") (name "Net-(WAGO13A-KL)") (class "Default")
      (node (ref "TIP27") (pin "C") (pinfunction "C_C") (pintype "passive"))
      (node (ref "WAGO13") (pin "1") (pinfunction "KL_1") (pintype "passive"))
    )
    (net (code "89") (name "Net-(WAGO13B-KL)") (class "Default")
      (node (ref "TIP26") (pin "C") (pinfunction "C_C") (pintype "passive"))
      (node (ref "WAGO13") (pin "2") (pinfunction "KL_2") (pintype "passive"))
    )
    (net (code "90") (name "Net-(WAGO14A-KL)") (class "Default")
      (node (ref "TIP29") (pin "C") (pinfunction "C_C") (pintype "passive"))
      (node (ref "WAGO14") (pin "1") (pinfunction "KL_1") (pintype "passive"))
    )
    (net (code "91") (name "Net-(WAGO14B-KL)") (class "Default")
      (node (ref "TIP28") (pin "C") (pinfunction "C_C") (pintype "passive"))
      (node (ref "WAGO14") (pin "2") (pinfunction "KL_2") (pintype "passive"))
    )
    (net (code "92") (name "Net-(WAGO15A-KL)") (class "Default")
      (node (ref "TIP31") (pin "C") (pinfunction "C_C") (pintype "passive"))
      (node (ref "WAGO15") (pin "1") (pinfunction "KL_1") (pintype "passive"))
    )
    (net (code "93") (name "Net-(WAGO15B-KL)") (class "Default")
      (node (ref "TIP30") (pin "C") (pinfunction "C_C") (pintype "passive"))
      (node (ref "WAGO15") (pin "2") (pinfunction "KL_2") (pintype "passive"))
    )
    (net (code "94") (name "Net-(WAGO16A-KL)") (class "Default")
      (node (ref "TIP33") (pin "C") (pinfunction "C_C") (pintype "passive"))
      (node (ref "WAGO16") (pin "1") (pinfunction "KL_1") (pintype "passive"))
    )
    (net (code "95") (name "Net-(WAGO16B-KL)") (class "Default")
      (node (ref "TIP32") (pin "C") (pinfunction "C_C") (pintype "passive"))
      (node (ref "WAGO16") (pin "2") (pinfunction "KL_2") (pintype "passive"))
    )
    (net (code "96") (name "Net-(WAGO17A-KL)") (class "Default")
      (node (ref "TIP35") (pin "C") (pinfunction "C_C") (pintype "passive"))
      (node (ref "WAGO17") (pin "1") (pinfunction "KL_1") (pintype "passive"))
    )
    (net (code "97") (name "Net-(WAGO17B-KL)") (class "Default")
      (node (ref "TIP34") (pin "C") (pinfunction "C_C") (pintype "passive"))
      (node (ref "WAGO17") (pin "2") (pinfunction "KL_2") (pintype "passive"))
    )
    (net (code "98") (name "Net-(WAGO18A-KL)") (class "Default")
      (node (ref "TIP37") (pin "C") (pinfunction "C_C") (pintype "passive"))
      (node (ref "WAGO18") (pin "1") (pinfunction "KL_1") (pintype "passive"))
    )
    (net (code "99") (name "Net-(WAGO18B-KL)") (class "Default")
      (node (ref "TIP36") (pin "C") (pinfunction "C_C") (pintype "passive"))
      (node (ref "WAGO18") (pin "2") (pinfunction "KL_2") (pintype "passive"))
    )
    (net (code "100") (name "Net-(WAGO19A-KL)") (class "Default")
      (node (ref "TIP39") (pin "C") (pinfunction "C_C") (pintype "passive"))
      (node (ref "WAGO19") (pin "1") (pinfunction "KL_1") (pintype "passive"))
    )
    (net (code "101") (name "Net-(WAGO19B-KL)") (class "Default")
      (node (ref "TIP38") (pin "C") (pinfunction "C_C") (pintype "passive"))
      (node (ref "WAGO19") (pin "2") (pinfunction "KL_2") (pintype "passive"))
    )
    (net (code "102") (name "Net-(WAGO20A-KL)") (class "Default")
      (node (ref "TIP41") (pin "C") (pinfunction "C_C") (pintype "passive"))
      (node (ref "WAGO20") (pin "1") (pinfunction "KL_1") (pintype "passive"))
    )
    (net (code "103") (name "Net-(WAGO20B-KL)") (class "Default")
      (node (ref "TIP40") (pin "C") (pinfunction "C_C") (pintype "passive"))
      (node (ref "WAGO20") (pin "2") (pinfunction "KL_2") (pintype "passive"))
    )
    (net (code "104") (name "Net-(WAGO21A-KL)") (class "Default")
      (node (ref "TIP43") (pin "C") (pinfunction "C_C") (pintype "passive"))
      (node (ref "WAGO21") (pin "1") (pinfunction "KL_1") (pintype "passive"))
    )
    (net (code "105") (name "Net-(WAGO21B-KL)") (class "Default")
      (node (ref "TIP42") (pin "C") (pinfunction "C_C") (pintype "passive"))
      (node (ref "WAGO21") (pin "2") (pinfunction "KL_2") (pintype "passive"))
    )
    (net (code "106") (name "Net-(WAGO22A-KL)") (class "Default")
      (node (ref "TIP45") (pin "C") (pinfunction "C_C") (pintype "passive"))
      (node (ref "WAGO22") (pin "1") (pinfunction "KL_1") (pintype "passive"))
    )
    (net (code "107") (name "Net-(WAGO22B-KL)") (class "Default")
      (node (ref "TIP44") (pin "C") (pinfunction "C_C") (pintype "passive"))
      (node (ref "WAGO22") (pin "2") (pinfunction "KL_2") (pintype "passive"))
    )
    (net (code "108") (name "Net-(WAGO23A-KL)") (class "Default")
      (node (ref "TIP47") (pin "C") (pinfunction "C_C") (pintype "passive"))
      (node (ref "WAGO23") (pin "1") (pinfunction "KL_1") (pintype "passive"))
    )
    (net (code "109") (name "Net-(WAGO23B-KL)") (class "Default")
      (node (ref "TIP46") (pin "C") (pinfunction "C_C") (pintype "passive"))
      (node (ref "WAGO23") (pin "2") (pinfunction "KL_2") (pintype "passive"))
    )
    (net (code "110") (name "Net-(WAGO24A-KL)") (class "Default")
      (node (ref "TIP51") (pin "C") (pinfunction "C_C") (pintype "passive"))
      (node (ref "WAGO24") (pin "1") (pinfunction "KL_1") (pintype "passive"))
    )
    (net (code "111") (name "Net-(WAGO24B-KL)") (class "Default")
      (node (ref "TIP50") (pin "C") (pinfunction "C_C") (pintype "passive"))
      (node (ref "WAGO24") (pin "2") (pinfunction "KL_2") (pintype "passive"))
    )
    (net (code "112") (name "unconnected-(FONTELEDS-Pad2)") (class "Default")
      (node (ref "FONTELEDS") (pin "2") (pinfunction "2_2") (pintype "passive"))
    )
    (net (code "113") (name "unconnected-(INPUTPLACA-Pad1)") (class "Default")
      (node (ref "INPUTPLACA") (pin "1") (pinfunction "1_1") (pintype "passive"))
    )
    (net (code "114") (name "unconnected-(INPUTPLACA-Pad6)") (class "Default")
      (node (ref "INPUTPLACA") (pin "6") (pinfunction "6_6") (pintype "passive"))
    )
  )
)
